# interlock_board.net
KiCad netlist of a schematic drawn in EAGLE
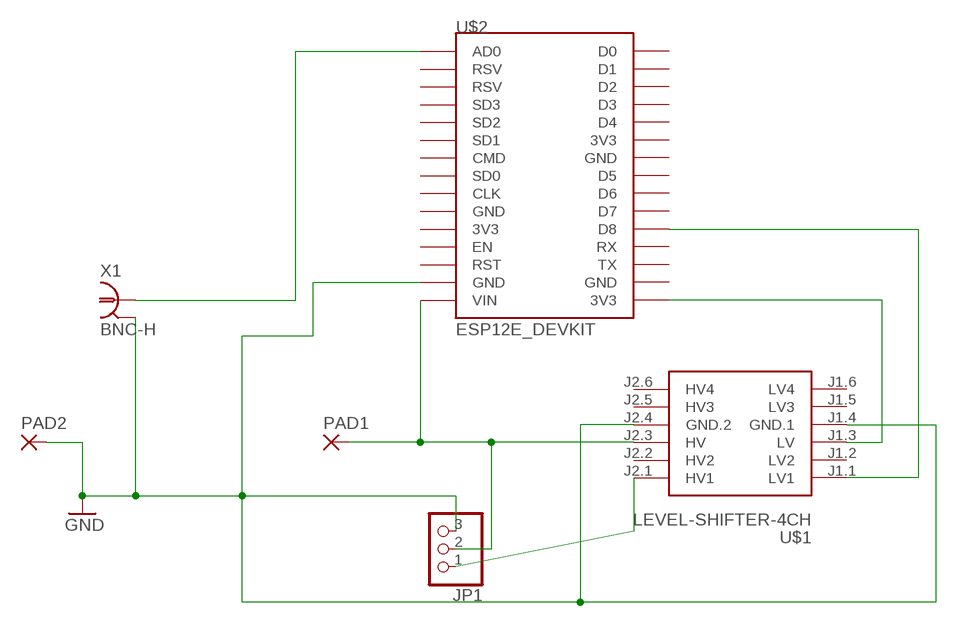
[diagram p0: schematic, sheet 1]

(export (version "E")
  (design (tool "Eeschema 10.0.6"))
  (components
    (comp (ref "JP1")
      (value "PINHD-1X3")
      (footprint "eagle-import:1X03")
      (libsource (lib "eagle-import") (part "PINHD-1X3"))
    )
    (comp (ref "PAD1")
      (value "2,54/0,9")
      (footprint "eagle-import:2,54_0,9")
      (libsource (lib "eagle-import") (part "2,54/0,9"))
    )
    (comp (ref "PAD2")
      (value "2,54/0,9")
      (footprint "eagle-import:2,54_0,9")
      (libsource (lib "eagle-import") (part "2,54/0,9"))
    )
    (comp (ref "U$1")
      (value "LEVEL-SHIFTER-4CH")
      (footprint "eagle-import:LEVEL-SHIFTER-4CH")
      (libsource (lib "eagle-import") (part "LEVEL-SHIFTER-4CH"))
    )
    (comp (ref "U$2")
      (value "ESP12E_DEVKIT")
      (footprint "eagle-import:ESP12E_DEVKIT")
      (libsource (lib "eagle-import") (part "ESP12E_DEVKIT"))
    )
    (comp (ref "X1")
      (value "BNC-H")
      (footprint "eagle-import:BNC90")
      (libsource (lib "eagle-import") (part "BNC-H"))
    )
  )
  (nets
    (net (code "1") (name "GND") (class "Default")
      (node (ref "JP1") (pin "3") (pinfunction "3_3") (pintype "passive"))
      (node (ref "PAD2") (pin "1") (pinfunction "P_1") (pintype "passive"))
      (node (ref "U$1") (pin "J1.4") (pinfunction "GND.1_J1.4") (pintype "power_in"))
      (node (ref "U$1") (pin "J2.4") (pinfunction "GND.2_J2.4") (pintype "power_in"))
      (node (ref "U$2") (pin "GND@1") (pinfunction "GND_GND@1") (pintype "bidirectional"))
      (node (ref "X1") (pin "2") (pinfunction "2_2") (pintype "passive"))
    )
    (net (code "2") (name "Net-(PAD1-P)") (class "Default")
      (node (ref "JP1") (pin "2") (pinfunction "2_2") (pintype "passive"))
      (node (ref "PAD1") (pin "1") (pinfunction "P_1") (pintype "passive"))
      (node (ref "U$1") (pin "J2.3") (pinfunction "HV_J2.3") (pintype "power_in"))
      (node (ref "U$2") (pin "VIN") (pinfunction "VIN_VIN") (pintype "bidirectional"))
    )
    (net (code "3") (name "Net-(U$1-HV1)") (class "Default")
      (node (ref "JP1") (pin "1") (pinfunction "1_1") (pintype "passive"))
      (node (ref "U$1") (pin "J2.1") (pinfunction "HV1_J2.1") (pintype "bidirectional"))
    )
    (net (code "4") (name "Net-(U$1-LV)") (class "Default")
      (node (ref "U$1") (pin "J1.3") (pinfunction "LV_J1.3") (pintype "power_in"))
      (node (ref "U$2") (pin "3V3@2") (pinfunction "3V3_3V3@2") (pintype "bidirectional"))
    )
    (net (code "5") (name "Net-(U$1-LV1)") (class "Default")
      (node (ref "U$1") (pin "J1.1") (pinfunction "LV1_J1.1") (pintype "bidirectional"))
      (node (ref "U$2") (pin "D8") (pinfunction "D8_D8") (pintype "bidirectional"))
    )
    (net (code "6") (name "Net-(U$2-PadAD0)") (class "Default")
      (node (ref "U$2") (pin "AD0") (pinfunction "AD0_AD0") (pintype "bidirectional"))
      (node (ref "X1") (pin "1") (pinfunction "1_1") (pintype "passive"))
    )
    (net (code "7") (name "unconnected-(U$1-HV2-PadJ2.2)") (class "Default")
      (node (ref "U$1") (pin "J2.2") (pinfunction "HV2_J2.2") (pintype "bidirectional"))
    )
    (net (code "8") (name "unconnected-(U$1-HV3-PadJ2.5)") (class "Default")
      (node (ref "U$1") (pin "J2.5") (pinfunction "HV3_J2.5") (pintype "bidirectional"))
    )
    (net (code "9") (name "unconnected-(U$1-HV4-PadJ2.6)") (class "Default")
      (node (ref "U$1") (pin "J2.6") (pinfunction "HV4_J2.6") (pintype "bidirectional"))
    )
    (net (code "10") (name "unconnected-(U$1-LV2-PadJ1.2)") (class "Default")
      (node (ref "U$1") (pin "J1.2") (pinfunction "LV2_J1.2") (pintype "bidirectional"))
    )
    (net (code "11") (name "unconnected-(U$1-LV3-PadJ1.5)") (class "Default")
      (node (ref "U$1") (pin "J1.5") (pinfunction "LV3_J1.5") (pintype "bidirectional"))
    )
    (net (code "12") (name "unconnected-(U$1-LV4-PadJ1.6)") (class "Default")
      (node (ref "U$1") (pin "J1.6") (pinfunction "LV4_J1.6") (pintype "bidirectional"))
    )
    (net (code "13") (name "unconnected-(U$2-3V3-Pad3V3@0)") (class "Default")
      (node (ref "U$2") (pin "3V3@0") (pinfunction "3V3_3V3@0") (pintype "bidirectional"))
    )
    (net (code "14") (name "unconnected-(U$2-3V3-Pad3V3@1)") (class "Default")
      (node (ref "U$2") (pin "3V3@1") (pinfunction "3V3_3V3@1") (pintype "bidirectional"))
    )
    (net (code "15") (name "unconnected-(U$2-GND-PadGND@0)") (class "Default")
      (node (ref "U$2") (pin "GND@0") (pinfunction "GND_GND@0") (pintype "bidirectional"))
    )
    (net (code "16") (name "unconnected-(U$2-GND-PadGND@2)") (class "Default")
      (node (ref "U$2") (pin "GND@2") (pinfunction "GND_GND@2") (pintype "bidirectional"))
    )
    (net (code "17") (name "unconnected-(U$2-GND-PadGND@3)") (class "Default")
      (node (ref "U$2") (pin "GND@3") (pinfunction "GND_GND@3") (pintype "bidirectional"))
    )
    (net (code "18") (name "unconnected-(U$2-PadCLK)") (class "Default")
      (node (ref "U$2") (pin "CLK") (pinfunction "CLK_CLK") (pintype "bidirectional"))
    )
    (net (code "19") (name "unconnected-(U$2-PadCMD)") (class "Default")
      (node (ref "U$2") (pin "CMD") (pinfunction "CMD_CMD") (pintype "bidirectional"))
    )
    (net (code "20") (name "unconnected-(U$2-PadD0)") (class "Default")
      (node (ref "U$2") (pin "D0") (pinfunction "D0_D0") (pintype "bidirectional"))
    )
    (net (code "21") (name "unconnected-(U$2-PadD1)") (class "Default")
      (node (ref "U$2") (pin "D1") (pinfunction "D1_D1") (pintype "bidirectional"))
    )
    (net (code "22") (name "unconnected-(U$2-PadD2)") (class "Default")
      (node (ref "U$2") (pin "D2") (pinfunction "D2_D2") (pintype "bidirectional"))
    )
    (net (code "23") (name "unconnected-(U$2-PadD3)") (class "Default")
      (node (ref "U$2") (pin "D3") (pinfunction "D3_D3") (pintype "bidirectional"))
    )
    (net (code "24") (name "unconnected-(U$2-PadD4)") (class "Default")
      (node (ref "U$2") (pin "D4") (pinfunction "D4_D4") (pintype "bidirectional"))
    )
    (net (code "25") (name "unconnected-(U$2-PadD5)") (class "Default")
      (node (ref "U$2") (pin "D5") (pinfunction "D5_D5") (pintype "bidirectional"))
    )
    (net (code "26") (name "unconnected-(U$2-PadD6)") (class "Default")
      (node (ref "U$2") (pin "D6") (pinfunction "D6_D6") (pintype "bidirectional"))
    )
    (net (code "27") (name "unconnected-(U$2-PadD7)") (class "Default")
      (node (ref "U$2") (pin "D7") (pinfunction "D7_D7") (pintype "bidirectional"))
    )
    (net (code "28") (name "unconnected-(U$2-PadEN)") (class "Default")
      (node (ref "U$2") (pin "EN") (pinfunction "EN_EN") (pintype "bidirectional"))
    )
    (net (code "29") (name "unconnected-(U$2-PadRST)") (class "Default")
      (node (ref "U$2") (pin "RST") (pinfunction "RST_RST") (pintype "bidirectional"))
    )
    (net (code "30") (name "unconnected-(U$2-PadRX)") (class "Default")
      (node (ref "U$2") (pin "RX") (pinfunction "RX_RX") (pintype "bidirectional"))
    )
    (net (code "31") (name "unconnected-(U$2-PadSD0)") (class "Default")
      (node (ref "U$2") (pin "SD0") (pinfunction "SD0_SD0") (pintype "bidirectional"))
    )
    (net (code "32") (name "unconnected-(U$2-PadSD1)") (class "Default")
      (node (ref "U$2") (pin "SD1") (pinfunction "SD1_SD1") (pintype "bidirectional"))
    )
    (net (code "33") (name "unconnected-(U$2-PadSD2)") (class "Default")
      (node (ref "U$2") (pin "SD2") (pinfunction "SD2_SD2") (pintype "bidirectional"))
    )
    (net (code "34") (name "unconnected-(U$2-PadSD3)") (class "Default")
      (node (ref "U$2") (pin "SD3") (pinfunction "SD3_SD3") (pintype "bidirectional"))
    )
    (net (code "35") (name "unconnected-(U$2-PadTX)") (class "Default")
      (node (ref "U$2") (pin "TX") (pinfunction "TX_TX") (pintype "bidirectional"))
    )
    (net (code "36") (name "unconnected-(U$2-RSV-PadRSV@0)") (class "Default")
      (node (ref "U$2") (pin "RSV@0") (pinfunction "RSV_RSV@0") (pintype "bidirectional"))
    )
    (net (code "37") (name "unconnected-(U$2-RSV-PadRSV@1)") (class "Default")
      (node (ref "U$2") (pin "RSV@1") (pinfunction "RSV_RSV@1") (pintype "bidirectional"))
    )
  )
)
